# 05-GPS_IMU_SENSORS.net
KiCad netlist of a schematic drawn in Altium Designer
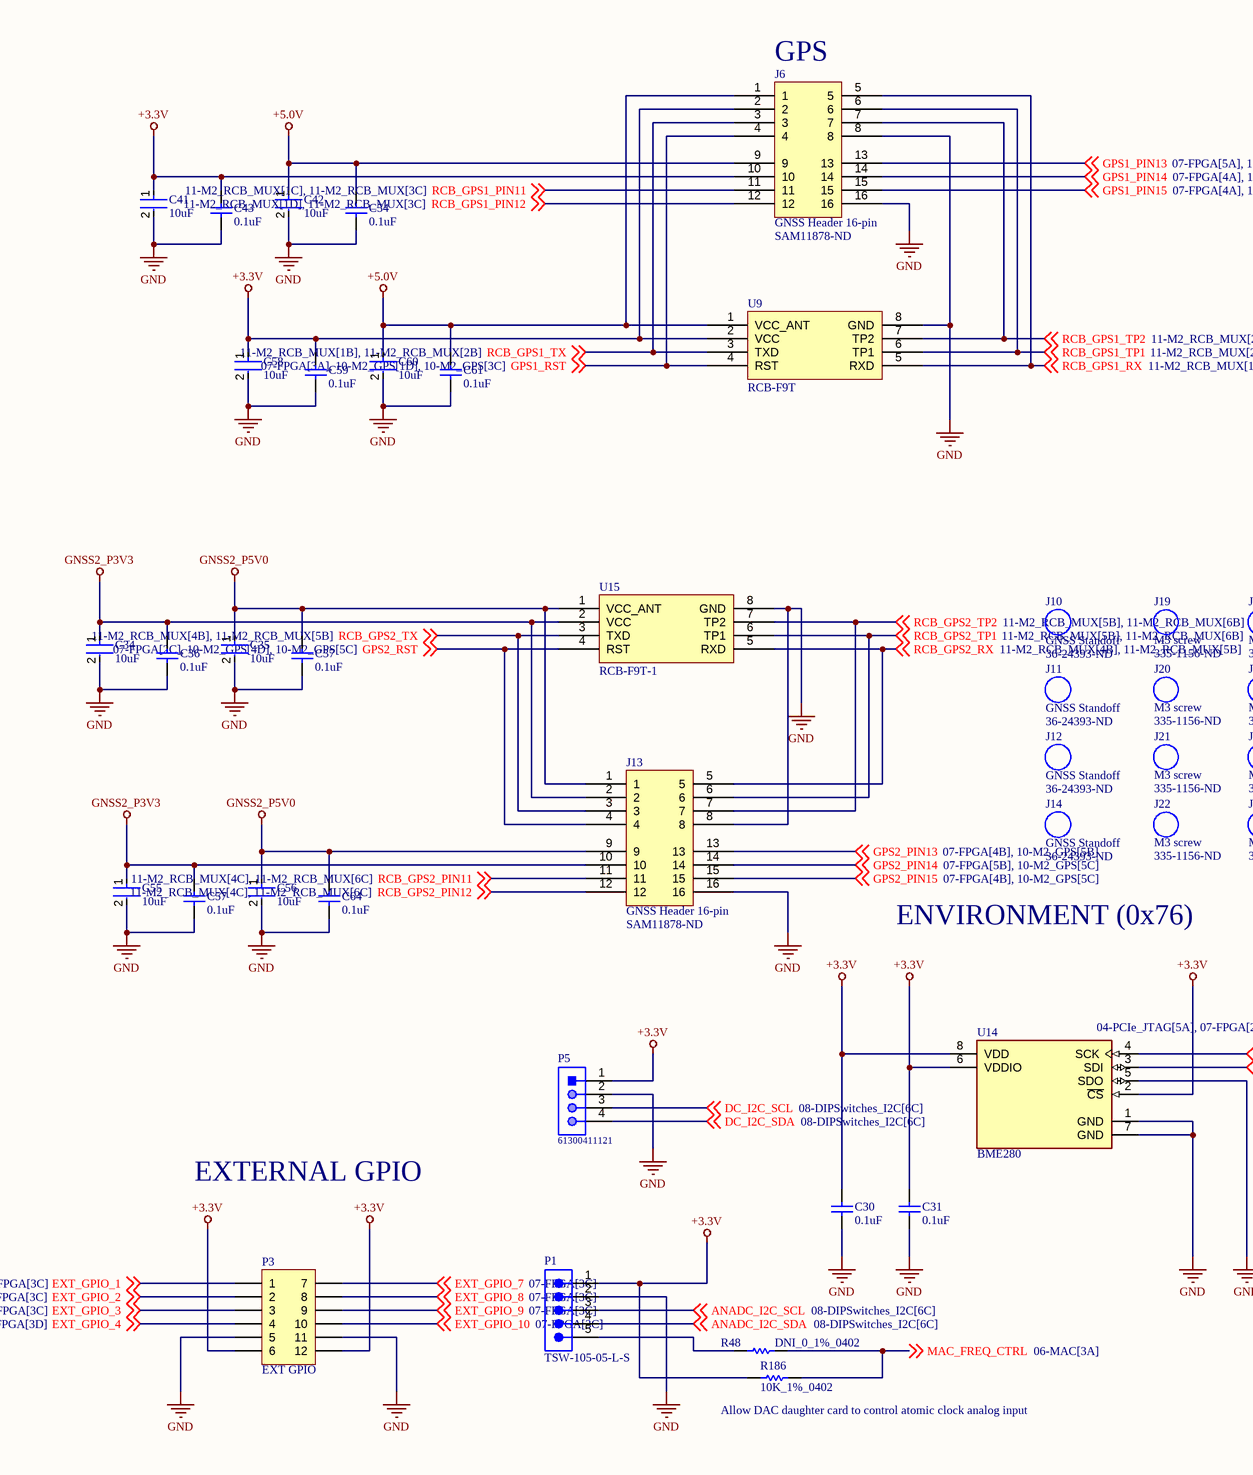
[diagram p0: 05-GPS_IMU_SENSORS.SchDoc, left]
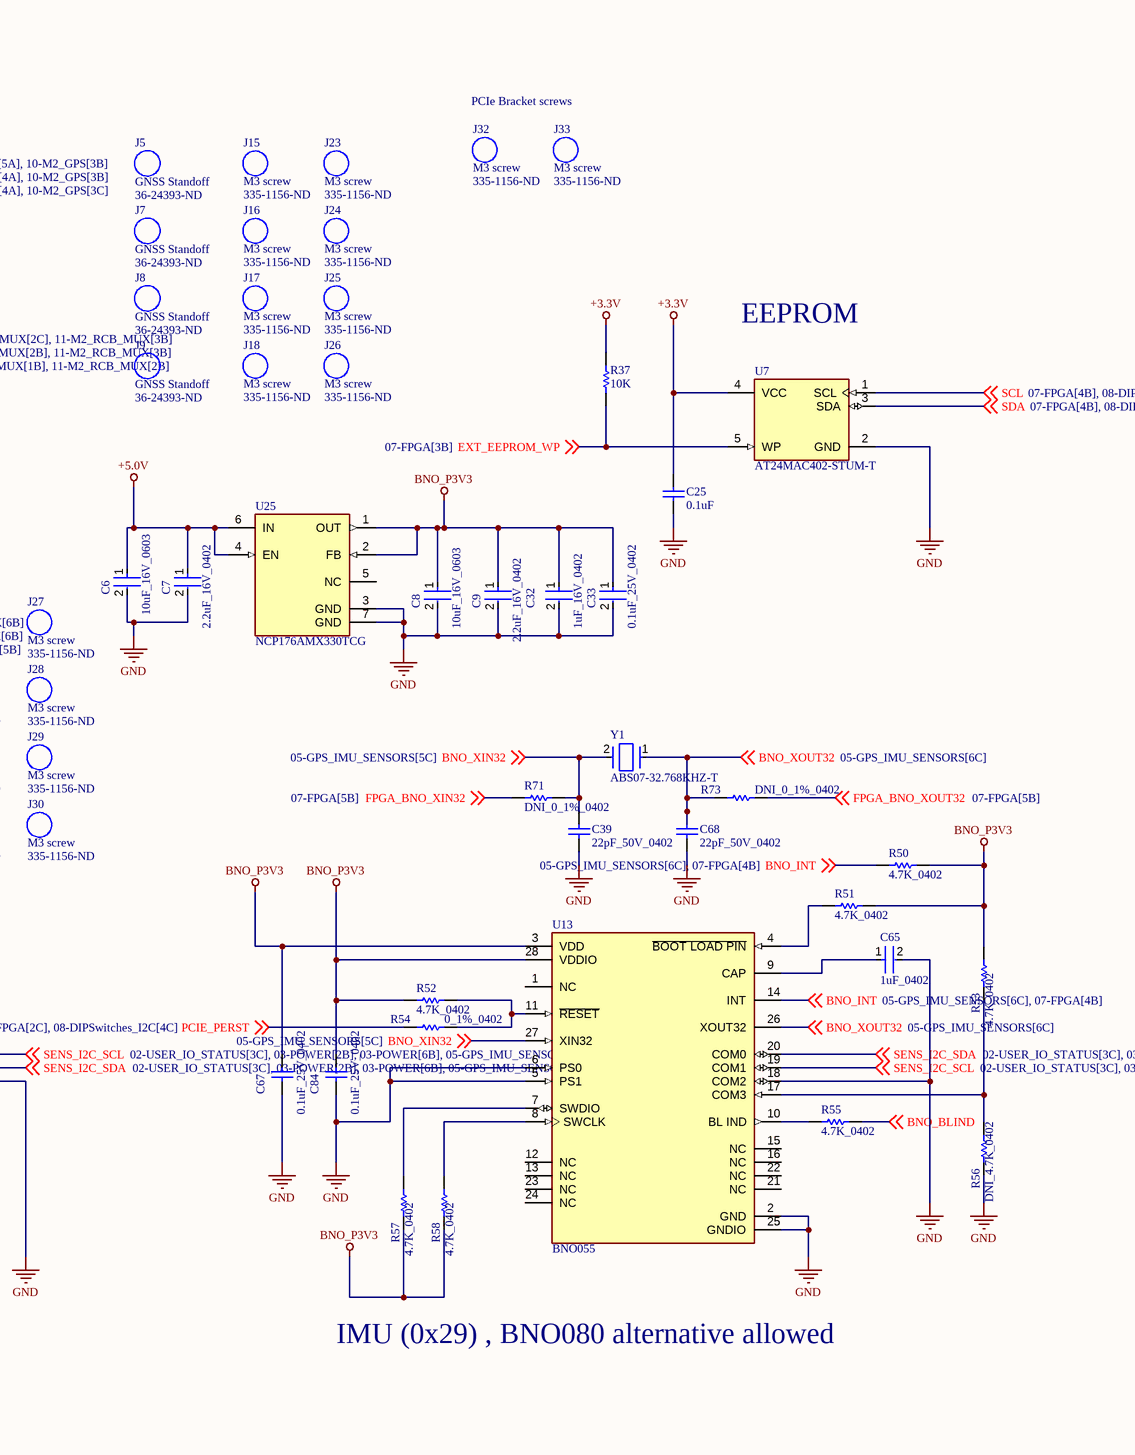
[diagram p1: 05-GPS_IMU_SENSORS.SchDoc, right]

(export (version "E")
  (design (tool "Eeschema 10.0.6"))
  (components
    (comp (ref "C6")
      (value "10uF_16V_0603")
      (footprint "FP-0603-L_1_6_0_2-W_0_8_0-MFG")
      (description "Multilayer Ceramic Capacitor 10uF 16V X5R 20% SMD 0603 T/R")
      (fields (field (name "TOLERANCE") "20%"))
      (libsource (lib "Altium Content Vault") (part "b4654b650e69147ec39a6b967a45e02"))
    )
    (comp (ref "C7")
      (value "2.2uF_16V_0402")
      (footprint "FP-C1005-050-0_05-IPC_A")
      (description "Multilayer Ceramic Capacitors 2.2μF ±10% 16V X5R SMD 0402")
      (fields (field (name "TOLERANCE") "10%"))
      (libsource (lib "Altium Content Vault") (part "b4654b650e69147ec39a6b967a45e02"))
    )
    (comp (ref "C8")
      (value "10uF_16V_0603")
      (footprint "FP-0603-L_1_6_0_2-W_0_8_0-MFG")
      (description "Multilayer Ceramic Capacitor 10uF 16V X5R 20% SMD 0603 T/R")
      (fields (field (name "TOLERANCE") "20%"))
      (libsource (lib "Altium Content Vault") (part "b4654b650e69147ec39a6b967a45e02"))
    )
    (comp (ref "C9")
      (value "2.2uF_16V_0402")
      (footprint "FP-C1005-050-0_05-IPC_A")
      (description "Multilayer Ceramic Capacitors 2.2μF ±10% 16V X5R SMD 0402")
      (fields (field (name "TOLERANCE") "10%"))
      (libsource (lib "Altium Content Vault") (part "b4654b650e69147ec39a6b967a45e02"))
    )
    (comp (ref "C25")
      (value "0.1uF")
      (footprint "CAPC1608X87X45ML20T05")
      (description "C0603X104K5RACAUTO")
      (fields (field (name "MANUFACTURER") "Kemet"))
      (libsource (lib "Altium Content Vault") (part "CAP"))
    )
    (comp (ref "C30")
      (value "0.1uF")
      (footprint "CAPC1608X87X45ML20T05")
      (description "C0603X104K5RACAUTO")
      (fields (field (name "MANUFACTURER") "Kemet"))
      (libsource (lib "Altium Content Vault") (part "CAP"))
    )
    (comp (ref "C31")
      (value "0.1uF")
      (footprint "CAPC1608X87X45ML20T05")
      (description "C0603X104K5RACAUTO")
      (fields (field (name "MANUFACTURER") "Kemet"))
      (libsource (lib "Altium Content Vault") (part "CAP"))
    )
    (comp (ref "C32")
      (value "1uF_16V_0402")
      (footprint "FP-0402-L_1_0_0_05-W_0_5-IPC_A")
      (description "None")
      (fields (field (name "TOLERANCE") "10%"))
      (libsource (lib "Altium Content Vault") (part "b4654b650e69147ec39a6b967a45e02"))
    )
    (comp (ref "C33")
      (value "0.1uF_25V_0402")
      (footprint "FP-0402-L_1_0_1-W_0_5_0_1-IPC_C")
      (description "General Purpose Ceramic Capacitor, 0402, 100nF, 10%, X7R, 15%, 25V")
      (fields (field (name "VOLTAGE") "25V") (field (name "TOLERANCE") "10%"))
      (libsource (lib "Altium Content Vault") (part "b4654b650e69147ec39a6b967a45e02"))
    )
    (comp (ref "C34")
      (value "10uF")
      (footprint "FP-MK212BG-MFG")
      (description "None")
      (fields (field (name "TOLERANCE") "10%") (field (name "VOLTAGE") "16V"))
      (libsource (lib "Altium Content Vault") (part "b4654b650e69147ec39a6b967a45e02"))
    )
    (comp (ref "C35")
      (value "10uF")
      (footprint "FP-MK212BG-MFG")
      (description "None")
      (fields (field (name "TOLERANCE") "10%") (field (name "VOLTAGE") "16V"))
      (libsource (lib "Altium Content Vault") (part "b4654b650e69147ec39a6b967a45e02"))
    )
    (comp (ref "C36")
      (value "0.1uF")
      (footprint "CAPC1608X87X45ML20T05")
      (description "C0603X104K5RACAUTO")
      (fields (field (name "MANUFACTURER") "Kemet"))
      (libsource (lib "Altium Content Vault") (part "CAP"))
    )
    (comp (ref "C37")
      (value "0.1uF")
      (footprint "CAPC1608X87X45ML20T05")
      (description "C0603X104K5RACAUTO")
      (fields (field (name "MANUFACTURER") "Kemet"))
      (libsource (lib "Altium Content Vault") (part "CAP"))
    )
    (comp (ref "C39")
      (value "22pF_50V_0402")
      (footprint "CAPC1005X55X25ML05T05")
      (description "Chip Capacitor, 22 pF, +/- 5%, 50 V, -55 to 125 degC, 0402 (1005 Metric), RoHS, Tape and Reel")
      (fields (field (name "MANUFACTURER") "Yageo") (field (name "TOLERANCE") "5%"))
      (libsource (lib "Altium Content Vault") (part "CAP-NP-2"))
    )
    (comp (ref "C41")
      (value "10uF")
      (footprint "FP-MK212BG-MFG")
      (description "None")
      (fields (field (name "TOLERANCE") "10%") (field (name "VOLTAGE") "16V"))
      (libsource (lib "Altium Content Vault") (part "b4654b650e69147ec39a6b967a45e02"))
    )
    (comp (ref "C42")
      (value "10uF")
      (footprint "FP-MK212BG-MFG")
      (description "None")
      (fields (field (name "TOLERANCE") "10%") (field (name "VOLTAGE") "16V"))
      (libsource (lib "Altium Content Vault") (part "b4654b650e69147ec39a6b967a45e02"))
    )
    (comp (ref "C43")
      (value "0.1uF")
      (footprint "CAPC1608X87X45ML20T05")
      (description "C0603X104K5RACAUTO")
      (fields (field (name "MANUFACTURER") "Kemet"))
      (libsource (lib "Altium Content Vault") (part "CAP"))
    )
    (comp (ref "C54")
      (value "0.1uF")
      (footprint "CAPC1608X87X45ML20T05")
      (description "C0603X104K5RACAUTO")
      (fields (field (name "MANUFACTURER") "Kemet"))
      (libsource (lib "Altium Content Vault") (part "CAP"))
    )
    (comp (ref "C55")
      (value "10uF")
      (footprint "FP-MK212BG-MFG")
      (description "None")
      (fields (field (name "TOLERANCE") "10%") (field (name "VOLTAGE") "16V"))
      (libsource (lib "Altium Content Vault") (part "b4654b650e69147ec39a6b967a45e02"))
    )
    (comp (ref "C56")
      (value "10uF")
      (footprint "FP-MK212BG-MFG")
      (description "None")
      (fields (field (name "TOLERANCE") "10%") (field (name "VOLTAGE") "16V"))
      (libsource (lib "Altium Content Vault") (part "b4654b650e69147ec39a6b967a45e02"))
    )
    (comp (ref "C57")
      (value "0.1uF")
      (footprint "CAPC1608X87X45ML20T05")
      (description "C0603X104K5RACAUTO")
      (fields (field (name "MANUFACTURER") "Kemet"))
      (libsource (lib "Altium Content Vault") (part "CAP"))
    )
    (comp (ref "C58")
      (value "10uF")
      (footprint "FP-MK212BG-MFG")
      (description "None")
      (fields (field (name "TOLERANCE") "10%") (field (name "VOLTAGE") "16V"))
      (libsource (lib "Altium Content Vault") (part "b4654b650e69147ec39a6b967a45e02"))
    )
    (comp (ref "C59")
      (value "0.1uF")
      (footprint "CAPC1608X87X45ML20T05")
      (description "C0603X104K5RACAUTO")
      (fields (field (name "MANUFACTURER") "Kemet"))
      (libsource (lib "Altium Content Vault") (part "CAP"))
    )
    (comp (ref "C60")
      (value "10uF")
      (footprint "FP-MK212BG-MFG")
      (description "None")
      (fields (field (name "TOLERANCE") "10%") (field (name "VOLTAGE") "16V"))
      (libsource (lib "Altium Content Vault") (part "b4654b650e69147ec39a6b967a45e02"))
    )
    (comp (ref "C61")
      (value "0.1uF")
      (footprint "CAPC1608X87X45ML20T05")
      (description "C0603X104K5RACAUTO")
      (fields (field (name "MANUFACTURER") "Kemet"))
      (libsource (lib "Altium Content Vault") (part "CAP"))
    )
    (comp (ref "C64")
      (value "0.1uF")
      (footprint "CAPC1608X87X45ML20T05")
      (description "C0603X104K5RACAUTO")
      (fields (field (name "MANUFACTURER") "Kemet"))
      (libsource (lib "Altium Content Vault") (part "CAP"))
    )
    (comp (ref "C65")
      (value "1uF_0402")
      (footprint "FP-0402-L_1_0_0_05-W_0_5-IPC_C")
      (description "None")
      (fields (field (name "TOLERANCE") "20%") (field (name "VOLTAGE") "16V"))
      (libsource (lib "Altium Content Vault") (part "b4654b650e69147ec39a6b967a45e02"))
    )
    (comp (ref "C67")
      (value "0.1uF_25V_0402")
      (footprint "CAPC1005X56X25NL10T15")
      (fields
        (field (name "PART NUMBER") "04023D104KAT2A")
        (field (name "MANUFACTURER") "AVX Interconnect / Elco")
      )
      (libsource (lib "Altium Content Vault") (part "CAP"))
    )
    (comp (ref "C68")
      (value "22pF_50V_0402")
      (footprint "CAPC1005X55X25ML05T05")
      (description "Chip Capacitor, 22 pF, +/- 5%, 50 V, -55 to 125 degC, 0402 (1005 Metric), RoHS, Tape and Reel")
      (fields (field (name "MANUFACTURER") "Yageo") (field (name "TOLERANCE") "5%"))
      (libsource (lib "Altium Content Vault") (part "CAP-NP-2"))
    )
    (comp (ref "C84")
      (value "0.1uF_25V_0402")
      (footprint "CAPC1005X56X25NL10T15")
      (fields
        (field (name "PART NUMBER") "04023D104KAT2A")
        (field (name "MANUFACTURER") "AVX Interconnect / Elco")
      )
      (libsource (lib "Altium Content Vault") (part "CAP"))
    )
    (comp (ref "J5")
      (value "GNSS Standoff")
      (fields (field (name "SUPPLIER PART NUMBER 1") "36-24393-ND"))
      (libsource (lib "FPGA_CONN") (part "GNSS Standoff"))
    )
    (comp (ref "J6")
      (value "GNSS Header 16-pin")
      (footprint "GNSS Header 16-pin")
      (fields (field (name "SUPPLIER PART NUMBER 1") "SAM11878-ND"))
      (libsource (lib "FPGA_CONN") (part "GNSS Header 16-pin"))
    )
    (comp (ref "J7")
      (value "GNSS Standoff")
      (fields (field (name "SUPPLIER PART NUMBER 1") "36-24393-ND"))
      (libsource (lib "FPGA_CONN") (part "GNSS Standoff"))
    )
    (comp (ref "J8")
      (value "GNSS Standoff")
      (fields (field (name "SUPPLIER PART NUMBER 1") "36-24393-ND"))
      (libsource (lib "FPGA_CONN") (part "GNSS Standoff"))
    )
    (comp (ref "J9")
      (value "GNSS Standoff")
      (fields (field (name "SUPPLIER PART NUMBER 1") "36-24393-ND"))
      (libsource (lib "FPGA_CONN") (part "GNSS Standoff"))
    )
    (comp (ref "J10")
      (value "GNSS Standoff")
      (fields (field (name "SUPPLIER PART NUMBER 1") "36-24393-ND"))
      (libsource (lib "FPGA_CONN") (part "GNSS Standoff"))
    )
    (comp (ref "J11")
      (value "GNSS Standoff")
      (fields (field (name "SUPPLIER PART NUMBER 1") "36-24393-ND"))
      (libsource (lib "FPGA_CONN") (part "GNSS Standoff"))
    )
    (comp (ref "J12")
      (value "GNSS Standoff")
      (fields (field (name "SUPPLIER PART NUMBER 1") "36-24393-ND"))
      (libsource (lib "FPGA_CONN") (part "GNSS Standoff"))
    )
    (comp (ref "J13")
      (value "GNSS Header 16-pin")
      (footprint "GNSS Header 16-pin")
      (fields (field (name "SUPPLIER PART NUMBER 1") "SAM11878-ND"))
      (libsource (lib "FPGA_CONN") (part "GNSS Header 16-pin"))
    )
    (comp (ref "J14")
      (value "GNSS Standoff")
      (fields (field (name "SUPPLIER PART NUMBER 1") "36-24393-ND"))
      (libsource (lib "FPGA_CONN") (part "GNSS Standoff"))
    )
    (comp (ref "J15")
      (value "M3 screw")
      (fields (field (name "SUPPLIER PART NUMBER 1") "335-1156-ND"))
      (libsource (lib "FPGA_CONN") (part "M3 screw"))
    )
    (comp (ref "J16")
      (value "M3 screw")
      (fields (field (name "SUPPLIER PART NUMBER 1") "335-1156-ND"))
      (libsource (lib "FPGA_CONN") (part "M3 screw"))
    )
    (comp (ref "J17")
      (value "M3 screw")
      (fields (field (name "SUPPLIER PART NUMBER 1") "335-1156-ND"))
      (libsource (lib "FPGA_CONN") (part "M3 screw"))
    )
    (comp (ref "J18")
      (value "M3 screw")
      (fields (field (name "SUPPLIER PART NUMBER 1") "335-1156-ND"))
      (libsource (lib "FPGA_CONN") (part "M3 screw"))
    )
    (comp (ref "J19")
      (value "M3 screw")
      (fields (field (name "SUPPLIER PART NUMBER 1") "335-1156-ND"))
      (libsource (lib "FPGA_CONN") (part "M3 screw"))
    )
    (comp (ref "J20")
      (value "M3 screw")
      (fields (field (name "SUPPLIER PART NUMBER 1") "335-1156-ND"))
      (libsource (lib "FPGA_CONN") (part "M3 screw"))
    )
    (comp (ref "J21")
      (value "M3 screw")
      (fields (field (name "SUPPLIER PART NUMBER 1") "335-1156-ND"))
      (libsource (lib "FPGA_CONN") (part "M3 screw"))
    )
    (comp (ref "J22")
      (value "M3 screw")
      (fields (field (name "SUPPLIER PART NUMBER 1") "335-1156-ND"))
      (libsource (lib "FPGA_CONN") (part "M3 screw"))
    )
    (comp (ref "J23")
      (value "M3 screw")
      (fields (field (name "SUPPLIER PART NUMBER 1") "335-1156-ND"))
      (libsource (lib "FPGA_CONN") (part "M3 screw"))
    )
    (comp (ref "J24")
      (value "M3 screw")
      (fields (field (name "SUPPLIER PART NUMBER 1") "335-1156-ND"))
      (libsource (lib "FPGA_CONN") (part "M3 screw"))
    )
    (comp (ref "J25")
      (value "M3 screw")
      (fields (field (name "SUPPLIER PART NUMBER 1") "335-1156-ND"))
      (libsource (lib "FPGA_CONN") (part "M3 screw"))
    )
    (comp (ref "J26")
      (value "M3 screw")
      (fields (field (name "SUPPLIER PART NUMBER 1") "335-1156-ND"))
      (libsource (lib "FPGA_CONN") (part "M3 screw"))
    )
    (comp (ref "J27")
      (value "M3 screw")
      (fields (field (name "SUPPLIER PART NUMBER 1") "335-1156-ND"))
      (libsource (lib "FPGA_CONN") (part "M3 screw"))
    )
    (comp (ref "J28")
      (value "M3 screw")
      (fields (field (name "SUPPLIER PART NUMBER 1") "335-1156-ND"))
      (libsource (lib "FPGA_CONN") (part "M3 screw"))
    )
    (comp (ref "J29")
      (value "M3 screw")
      (fields (field (name "SUPPLIER PART NUMBER 1") "335-1156-ND"))
      (libsource (lib "FPGA_CONN") (part "M3 screw"))
    )
    (comp (ref "J30")
      (value "M3 screw")
      (fields (field (name "SUPPLIER PART NUMBER 1") "335-1156-ND"))
      (libsource (lib "FPGA_CONN") (part "M3 screw"))
    )
    (comp (ref "J32")
      (value "M3 screw")
      (fields (field (name "SUPPLIER PART NUMBER 1") "335-1156-ND"))
      (libsource (lib "FPGA_CONN") (part "M3 screw"))
    )
    (comp (ref "J33")
      (value "M3 screw")
      (fields (field (name "SUPPLIER PART NUMBER 1") "335-1156-ND"))
      (libsource (lib "FPGA_CONN") (part "M3 screw"))
    )
    (comp (ref "P1")
      (value "TSW-105-05-L-S")
      (footprint "SMTC-TSW-105-05-X-S")
      (description "0.025\" SQ Post Header, Through-hole, Vertical, -55 to 125 degC, 2.54 mm Pitch, 5-Pin, Male, RoHS")
      (fields (field (name "MANUFACTURER") "Samtec"))
      (libsource (lib "Altium Content Vault") (part "SMTC-TSW-105-05-X-S"))
    )
    (comp (ref "P3")
      (value "EXT GPIO")
      (footprint "HDR2X6_CEN")
      (description "Header, 6-Pin, Dual row")
      (fields (field (name "PUBLISHER") "Altium Limited"))
      (libsource (lib "Miscellaneous Connectors") (part "Header 6X2A"))
    )
    (comp (ref "P5")
      (value "61300411121")
      (footprint "61300411121")
      (description "THT Vertical Pin Header WR-PHD, Pitch 2.54 mm, Single Row, 4 pins")
      (fields (field (name "MANUFACTURER") "Wurth Elektronik") (field (name "PUBLISHER") "WurthElektronik"))
      (libsource (lib "Altium Content Vault") (part "WE-CN-1P-M-R4"))
    )
    (comp (ref "R37")
      (value "10K")
      (footprint "RESC1608X55X30LL15T20")
      (fields (field (name "TOLERANCE") "±1%") (field (name "MANUFACTURER") "Stackpole-Electronics-Inc."))
      (libsource (lib "Altium Content Vault") (part "RES-2"))
    )
    (comp (ref "R48")
      (value "DNI_0_1%_0402")
      (footprint "RESC1005X40X25LL05T05")
      (description "Chip Resistor, 0 Ohm, 0.1 W, -55 to 155 degC, 0402 (1005 Metric), RoHS, Tape and Reel")
      (fields (field (name "MANUFACTURER") "Panasonic") (field (name "TOLERANCE") "5%"))
      (libsource (lib "Altium Content Vault") (part "RES-2"))
    )
    (comp (ref "R50")
      (value "4.7K_0402")
      (footprint "RESC1005X40X25LL05T05")
      (description "Chip Resistor, 4.7 KOhm, +/- 1%, 0.1 W, -55 to 155 degC, 0402 (1005 Metric), RoHS, Tape and Reel")
      (fields (field (name "TOLERANCE") "1%") (field (name "PARTNUMBER") "ERJ-2RKF4701X"))
      (libsource (lib "Altium Content Vault") (part "RES-2"))
    )
    (comp (ref "R51")
      (value "4.7K_0402")
      (footprint "RESC1005X40X25LL05T05")
      (description "Chip Resistor, 4.7 KOhm, +/- 1%, 0.1 W, -55 to 155 degC, 0402 (1005 Metric), RoHS, Tape and Reel")
      (fields (field (name "TOLERANCE") "1%") (field (name "PARTNUMBER") "ERJ-2RKF4701X"))
      (libsource (lib "Altium Content Vault") (part "RES-2"))
    )
    (comp (ref "R52")
      (value "4.7K_0402")
      (footprint "RESC1005X40X25LL05T05")
      (description "Chip Resistor, 4.7 KOhm, +/- 1%, 0.1 W, -55 to 155 degC, 0402 (1005 Metric), RoHS, Tape and Reel")
      (fields (field (name "TOLERANCE") "1%") (field (name "PARTNUMBER") "ERJ-2RKF4701X"))
      (libsource (lib "Altium Content Vault") (part "RES-2"))
    )
    (comp (ref "R53")
      (value "4.7K_0402")
      (footprint "RESC1005X40X25LL05T05")
      (description "Chip Resistor, 4.7 KOhm, +/- 1%, 0.1 W, -55 to 155 degC, 0402 (1005 Metric), RoHS, Tape and Reel")
      (fields (field (name "TOLERANCE") "1%") (field (name "PARTNUMBER") "ERJ-2RKF4701X"))
      (libsource (lib "Altium Content Vault") (part "RES-2"))
    )
    (comp (ref "R54")
      (value "0_1%_0402")
      (footprint "RESC1005X40X25LL05T05")
      (description "Chip Resistor, 0 Ohm, 0.1 W, -55 to 155 degC, 0402 (1005 Metric), RoHS, Tape and Reel")
      (fields (field (name "MANUFACTURER") "Panasonic") (field (name "TOLERANCE") "5%"))
      (libsource (lib "Altium Content Vault") (part "RES-2"))
    )
    (comp (ref "R55")
      (value "4.7K_0402")
      (footprint "RESC1005X40X25LL05T05")
      (description "Chip Resistor, 4.7 KOhm, +/- 1%, 0.1 W, -55 to 155 degC, 0402 (1005 Metric), RoHS, Tape and Reel")
      (fields (field (name "TOLERANCE") "1%") (field (name "PARTNUMBER") "ERJ-2RKF4701X"))
      (libsource (lib "Altium Content Vault") (part "RES-2"))
    )
    (comp (ref "R56")
      (value "DNI_4.7K_0402")
      (footprint "RESC1005X40X25LL05T05")
      (description "Chip Resistor, 4.7 KOhm, +/- 1%, 0.1 W, -55 to 155 degC, 0402 (1005 Metric), RoHS, Tape and Reel")
      (fields (field (name "TOLERANCE") "1%") (field (name "PARTNUMBER") "ERJ-2RKF4701X"))
      (libsource (lib "Altium Content Vault") (part "RES-2"))
    )
    (comp (ref "R57")
      (value "4.7K_0402")
      (footprint "RESC1005X40X25LL05T05")
      (description "Chip Resistor, 4.7 KOhm, +/- 1%, 0.1 W, -55 to 155 degC, 0402 (1005 Metric), RoHS, Tape and Reel")
      (fields (field (name "TOLERANCE") "1%") (field (name "PARTNUMBER") "ERJ-2RKF4701X"))
      (libsource (lib "Altium Content Vault") (part "RES-2"))
    )
    (comp (ref "R58")
      (value "4.7K_0402")
      (footprint "RESC1005X40X25LL05T05")
      (description "Chip Resistor, 4.7 KOhm, +/- 1%, 0.1 W, -55 to 155 degC, 0402 (1005 Metric), RoHS, Tape and Reel")
      (fields (field (name "TOLERANCE") "1%") (field (name "PARTNUMBER") "ERJ-2RKF4701X"))
      (libsource (lib "Altium Content Vault") (part "RES-2"))
    )
    (comp (ref "R71")
      (value "DNI_0_1%_0402")
      (footprint "RESC1005X40X25LL05T05")
      (description "Chip Resistor, 0 Ohm, 0.1 W, -55 to 155 degC, 0402 (1005 Metric), RoHS, Tape and Reel")
      (fields (field (name "MANUFACTURER") "Panasonic") (field (name "TOLERANCE") "5%"))
      (libsource (lib "Altium Content Vault") (part "RES-2"))
    )
    (comp (ref "R73")
      (value "DNI_0_1%_0402")
      (footprint "RESC1005X40X25LL05T05")
      (description "Chip Resistor, 0 Ohm, 0.1 W, -55 to 155 degC, 0402 (1005 Metric), RoHS, Tape and Reel")
      (fields (field (name "MANUFACTURER") "Panasonic") (field (name "TOLERANCE") "5%"))
      (libsource (lib "Altium Content Vault") (part "RES-2"))
    )
    (comp (ref "R186")
      (value "10K_1%_0402")
      (footprint "RESC1005X40X25LL05T10")
      (fields (field (name "PART NUMBER") "RC0402FR-0710KL") (field (name "MANUFACTURER") "Yageo / Phycomp"))
      (libsource (lib "Altium Content Vault") (part "RES"))
    )
    (comp (ref "U7")
      (value "AT24MAC402-STUM-T")
      (footprint "FP-5TS1-IPC_C")
      (description "IC EEPROM 2K I2C 1MHZ SOT23-5")
      (fields
        (field (name "MANUFACTURER") "Microchip")
        (field (name "OCTOPART") "https://octopart.com/at24mac402-stum-t-microchip-77758112")
      )
      (libsource (lib "Altium Content Vault") (part "93fe34f5f049140596bab6421a6454b"))
    )
    (comp (ref "U9")
      (value "RCB-F9T")
      (footprint "GNSS")
      (description "MOD, GPS")
      (fields (field (name "VELENTIUM PART NUM") "<V PART NUM>"))
      (libsource (lib "Modules") (part "RCB-F9T"))
    )
    (comp (ref "U13")
      (value "BNO055")
      (footprint "FP-BNO055-MFG")
      (description "IMU ACCEL/GYRO/MAG I2C 28LGA")
      (libsource (lib "Altium Content Vault") (part "ba837af00a0b6167256f888b31462b1"))
    )
    (comp (ref "U14")
      (value "BME280")
      (footprint "FP-BME280-MFG")
      (description "SENSOR PRESSURE HUMIDITY TEMP")
      (libsource (lib "Altium Content Vault") (part "d58e2f6669bc67e6a2bc6a28610ca79"))
    )
    (comp (ref "U15")
      (value "RCB-F9T-1")
      (footprint "GNSS")
      (description "MOD, GPS")
      (fields (field (name "VELENTIUM PART NUM") "<V PART NUM>"))
      (libsource (lib "Modules") (part "RCB-F9T"))
    )
    (comp (ref "U25")
      (value "NCP176AMX330TCG")
      (footprint "FP-711AT-MFG")
      (description "IC REG LINEAR 3.3V 500MA 6XDFN")
      (fields
        (field (name "MANUFACTURER") "ON Semiconductor")
        (field (name "OCTOPART") "https://octopart.com/ncp176amx330tcg-on+semiconductor-61522616")
      )
      (libsource (lib "Altium Content Vault") (part "a38d0f79c2a9f01c07a7e52882ed186"))
    )
    (comp (ref "Y1")
      (value "ABS07-32.768KHZ-T")
      (footprint "FP-ABS07-MFG")
      (description "Crystal 32.768kHz ±20ppm (Tol) 12.5pF FUND 70kΩ 2-Pin CSMD T/R")
      (fields (field (name "TOLERANCE") "20ppm"))
      (libsource (lib "Altium Content Vault") (part "c23a69dc6c9e2f18f2079038eb95dd1"))
    )
  )
  (nets
    (net (code "1") (name "+3.3V") (class "Default")
      (node (ref "C25") (pin "2") (pinfunction "2_2") (pintype "passive"))
      (node (ref "C30") (pin "2") (pinfunction "2_2") (pintype "passive"))
      (node (ref "C31") (pin "2") (pinfunction "2_2") (pintype "passive"))
      (node (ref "C41") (pin "1") (pinfunction "1_1") (pintype "passive"))
      (node (ref "C43") (pin "2") (pinfunction "2_2") (pintype "passive"))
      (node (ref "C58") (pin "1") (pinfunction "1_1") (pintype "passive"))
      (node (ref "C59") (pin "2") (pinfunction "2_2") (pintype "passive"))
      (node (ref "J6") (pin "10") (pinfunction "10_10") (pintype "passive"))
      (node (ref "J6") (pin "2") (pinfunction "2_2") (pintype "passive"))
      (node (ref "P1") (pin "1") (pinfunction "1_1") (pintype "passive"))
      (node (ref "P3") (pin "12") (pinfunction "12_12") (pintype "passive"))
      (node (ref "P3") (pin "6") (pinfunction "6_6") (pintype "passive"))
      (node (ref "P5") (pin "1") (pinfunction "1_1") (pintype "passive"))
      (node (ref "R186") (pin "1") (pinfunction "1_1") (pintype "passive"))
      (node (ref "R37") (pin "2") (pinfunction "2_2") (pintype "passive"))
      (node (ref "U14") (pin "2") (pinfunction "~{CS}_2") (pintype "input"))
      (node (ref "U14") (pin "6") (pinfunction "VDDIO_6") (pintype "power_in"))
      (node (ref "U14") (pin "8") (pinfunction "VDD_8") (pintype "power_in"))
      (node (ref "U7") (pin "4") (pinfunction "VCC_4") (pintype "power_in"))
      (node (ref "U9") (pin "2") (pinfunction "VCC_2") (pintype "passive"))
    )
    (net (code "2") (name "+5.0V") (class "Default")
      (node (ref "C42") (pin "1") (pinfunction "1_1") (pintype "passive"))
      (node (ref "C54") (pin "2") (pinfunction "2_2") (pintype "passive"))
      (node (ref "C6") (pin "1") (pinfunction "1_1") (pintype "passive"))
      (node (ref "C60") (pin "1") (pinfunction "1_1") (pintype "passive"))
      (node (ref "C61") (pin "2") (pinfunction "2_2") (pintype "passive"))
      (node (ref "C7") (pin "1") (pinfunction "1_1") (pintype "passive"))
      (node (ref "J6") (pin "1") (pinfunction "1_1") (pintype "passive"))
      (node (ref "J6") (pin "9") (pinfunction "9_9") (pintype "passive"))
      (node (ref "U25") (pin "4") (pinfunction "EN_4") (pintype "input"))
      (node (ref "U25") (pin "6") (pinfunction "IN_6") (pintype "power_in"))
      (node (ref "U9") (pin "1") (pinfunction "VCC_ANT_1") (pintype "passive"))
    )
    (net (code "3") (name "ANADC_I2C_SCL") (class "Default")
      (node (ref "P1") (pin "3") (pinfunction "3_3") (pintype "passive"))
    )
    (net (code "4") (name "ANADC_I2C_SDA") (class "Default")
      (node (ref "P1") (pin "4") (pinfunction "4_4") (pintype "passive"))
    )
    (net (code "5") (name "BNO_BLIND") (class "Default")
      (node (ref "R55") (pin "1") (pinfunction "1_1") (pintype "passive"))
    )
    (net (code "6") (name "BNO_INT") (class "Default")
      (node (ref "R50") (pin "2") (pinfunction "2_2") (pintype "passive"))
      (node (ref "U13") (pin "14") (pinfunction "INT_14") (pintype "passive"))
    )
    (net (code "7") (name "BNO_P3V3") (class "Default")
      (node (ref "C32") (pin "1") (pinfunction "1_1") (pintype "passive"))
      (node (ref "C33") (pin "1") (pinfunction "1_1") (pintype "passive"))
      (node (ref "C67") (pin "2") (pinfunction "2_2") (pintype "passive"))
      (node (ref "C8") (pin "1") (pinfunction "1_1") (pintype "passive"))
      (node (ref "C84") (pin "2") (pinfunction "2_2") (pintype "passive"))
      (node (ref "C9") (pin "1") (pinfunction "1_1") (pintype "passive"))
      (node (ref "R50") (pin "1") (pinfunction "1_1") (pintype "passive"))
      (node (ref "R51") (pin "1") (pinfunction "1_1") (pintype "passive"))
      (node (ref "R52") (pin "2") (pinfunction "2_2") (pintype "passive"))
      (node (ref "R53") (pin "2") (pinfunction "2_2") (pintype "passive"))
      (node (ref "R57") (pin "1") (pinfunction "1_1") (pintype "passive"))
      (node (ref "R58") (pin "1") (pinfunction "1_1") (pintype "passive"))
      (node (ref "U13") (pin "28") (pinfunction "VDDIO_28") (pintype "power_in"))
      (node (ref "U13") (pin "3") (pinfunction "VDD_3") (pintype "power_in"))
      (node (ref "U25") (pin "1") (pinfunction "OUT_1") (pintype "output"))
      (node (ref "U25") (pin "2") (pinfunction "FB_2") (pintype "input"))
    )
    (net (code "8") (name "BNO_XIN32") (class "Default")
      (node (ref "C39") (pin "2") (pinfunction "2_2") (pintype "passive"))
      (node (ref "R71") (pin "1") (pinfunction "1_1") (pintype "passive"))
      (node (ref "U13") (pin "27") (pinfunction "XIN32_27") (pintype "input"))
      (node (ref "Y1") (pin "2") (pinfunction "2_2") (pintype "passive"))
    )
    (net (code "9") (name "BNO_XOUT32") (class "Default")
      (node (ref "C68") (pin "2") (pinfunction "2_2") (pintype "passive"))
      (node (ref "R73") (pin "1") (pinfunction "1_1") (pintype "passive"))
      (node (ref "U13") (pin "26") (pinfunction "XOUT32_26") (pintype "passive"))
      (node (ref "Y1") (pin "1") (pinfunction "1_1") (pintype "passive"))
    )
    (net (code "10") (name "DC_I2C_SCL") (class "Default")
      (node (ref "P5") (pin "3") (pinfunction "3_3") (pintype "passive"))
    )
    (net (code "11") (name "DC_I2C_SDA") (class "Default")
      (node (ref "P5") (pin "4") (pinfunction "4_4") (pintype "passive"))
    )
    (net (code "12") (name "EXT_EEPROM_WP") (class "Default")
      (node (ref "R37") (pin "1") (pinfunction "1_1") (pintype "passive"))
      (node (ref "U7") (pin "5") (pinfunction "WP_5") (pintype "input"))
    )
    (net (code "13") (name "EXT_GPIO_1") (class "Default")
      (node (ref "P3") (pin "1") (pinfunction "1_1") (pintype "passive"))
    )
    (net (code "14") (name "EXT_GPIO_2") (class "Default")
      (node (ref "P3") (pin "2") (pinfunction "2_2") (pintype "passive"))
    )
    (net (code "15") (name "EXT_GPIO_3") (class "Default")
      (node (ref "P3") (pin "3") (pinfunction "3_3") (pintype "passive"))
    )
    (net (code "16") (name "EXT_GPIO_4") (class "Default")
      (node (ref "P3") (pin "4") (pinfunction "4_4") (pintype "passive"))
    )
    (net (code "17") (name "EXT_GPIO_7") (class "Default")
      (node (ref "P3") (pin "7") (pinfunction "7_7") (pintype "passive"))
    )
    (net (code "18") (name "EXT_GPIO_8") (class "Default")
      (node (ref "P3") (pin "8") (pinfunction "8_8") (pintype "passive"))
    )
    (net (code "19") (name "EXT_GPIO_9") (class "Default")
      (node (ref "P3") (pin "9") (pinfunction "9_9") (pintype "passive"))
    )
    (net (code "20") (name "EXT_GPIO_10") (class "Default")
      (node (ref "P3") (pin "10") (pinfunction "10_10") (pintype "passive"))
    )
    (net (code "21") (name "FPGA_BNO_XIN32") (class "Default")
      (node (ref "R71") (pin "2") (pinfunction "2_2") (pintype "passive"))
    )
    (net (code "22") (name "FPGA_BNO_XOUT32") (class "Default")
      (node (ref "R73") (pin "2") (pinfunction "2_2") (pintype "passive"))
    )
    (net (code "23") (name "GND") (class "Default")
      (node (ref "C25") (pin "1") (pinfunction "1_1") (pintype "passive"))
      (node (ref "C30") (pin "1") (pinfunction "1_1") (pintype "passive"))
      (node (ref "C31") (pin "1") (pinfunction "1_1") (pintype "passive"))
      (node (ref "C32") (pin "2") (pinfunction "2_2") (pintype "passive"))
      (node (ref "C33") (pin "2") (pinfunction "2_2") (pintype "passive"))
      (node (ref "C34") (pin "2") (pinfunction "2_2") (pintype "passive"))
      (node (ref "C35") (pin "2") (pinfunction "2_2") (pintype "passive"))
      (node (ref "C36") (pin "1") (pinfunction "1_1") (pintype "passive"))
      (node (ref "C37") (pin "1") (pinfunction "1_1") (pintype "passive"))
      (node (ref "C39") (pin "1") (pinfunction "1_1") (pintype "passive"))
      (node (ref "C41") (pin "2") (pinfunction "2_2") (pintype "passive"))
      (node (ref "C42") (pin "2") (pinfunction "2_2") (pintype "passive"))
      (node (ref "C43") (pin "1") (pinfunction "1_1") (pintype "passive"))
      (node (ref "C54") (pin "1") (pinfunction "1_1") (pintype "passive"))
      (node (ref "C55") (pin "2") (pinfunction "2_2") (pintype "passive"))
      (node (ref "C56") (pin "2") (pinfunction "2_2") (pintype "passive"))
      (node (ref "C57") (pin "1") (pinfunction "1_1") (pintype "passive"))
      (node (ref "C58") (pin "2") (pinfunction "2_2") (pintype "passive"))
      (node (ref "C59") (pin "1") (pinfunction "1_1") (pintype "passive"))
      (node (ref "C6") (pin "2") (pinfunction "2_2") (pintype "passive"))
      (node (ref "C60") (pin "2") (pinfunction "2_2") (pintype "passive"))
      (node (ref "C61") (pin "1") (pinfunction "1_1") (pintype "passive"))
      (node (ref "C64") (pin "1") (pinfunction "1_1") (pintype "passive"))
      (node (ref "C65") (pin "2") (pinfunction "2_2") (pintype "passive"))
      (node (ref "C67") (pin "1") (pinfunction "1_1") (pintype "passive"))
      (node (ref "C68") (pin "1") (pinfunction "1_1") (pintype "passive"))
      (node (ref "C7") (pin "2") (pinfunction "2_2") (pintype "passive"))
      (node (ref "C8") (pin "2") (pinfunction "2_2") (pintype "passive"))
      (node (ref "C84") (pin "1") (pinfunction "1_1") (pintype "passive"))
      (node (ref "C9") (pin "2") (pinfunction "2_2") (pintype "passive"))
      (node (ref "J13") (pin "16") (pinfunction "16_16") (pintype "passive"))
      (node (ref "J13") (pin "8") (pinfunction "8_8") (pintype "passive"))
      (node (ref "J6") (pin "16") (pinfunction "16_16") (pintype "passive"))
      (node (ref "J6") (pin "8") (pinfunction "8_8") (pintype "passive"))
      (node (ref "P1") (pin "2") (pinfunction "2_2") (pintype "passive"))
      (node (ref "P3") (pin "11") (pinfunction "11_11") (pintype "passive"))
      (node (ref "P3") (pin "5") (pinfunction "5_5") (pintype "passive"))
      (node (ref "P5") (pin "2") (pinfunction "2_2") (pintype "passive"))
      (node (ref "R56") (pin "1") (pinfunction "1_1") (pintype "passive"))
      (node (ref "U13") (pin "18") (pinfunction "COM2_18") (pintype "bidirectional"))
      (node (ref "U13") (pin "2") (pinfunction "GND_2") (pintype "power_in"))
      (node (ref "U13") (pin "25") (pinfunction "GNDIO_25") (pintype "power_in"))
      (node (ref "U13") (pin "5") (pinfunction "PS1_5") (pintype "input"))
      (node (ref "U13") (pin "6") (pinfunction "PS0_6") (pintype "input"))
      (node (ref "U14") (pin "1") (pinfunction "GND_1") (pintype "power_in"))
      (node (ref "U14") (pin "5") (pinfunction "SDO_5") (pintype "bidirectional"))
      (node (ref "U14") (pin "7") (pinfunction "GND_7") (pintype "power_in"))
      (node (ref "U15") (pin "8") (pinfunction "GND_8") (pintype "passive"))
      (node (ref "U25") (pin "3") (pinfunction "GND_3") (pintype "power_in"))
      (node (ref "U25") (pin "7") (pinfunction "GND_7") (pintype "power_in"))
      (node (ref "U7") (pin "2") (pinfunction "GND_2") (pintype "power_in"))
      (node (ref "U9") (pin "8") (pinfunction "GND_8") (pintype "passive"))
    )
    (net (code "24") (name "GNSS2_P3V3") (class "Default")
      (node (ref "C34") (pin "1") (pinfunction "1_1") (pintype "passive"))
      (node (ref "C36") (pin "2") (pinfunction "2_2") (pintype "passive"))
      (node (ref "C55") (pin "1") (pinfunction "1_1") (pintype "passive"))
      (node (ref "C57") (pin "2") (pinfunction "2_2") (pintype "passive"))
      (node (ref "J13") (pin "10") (pinfunction "10_10") (pintype "passive"))
      (node (ref "J13") (pin "2") (pinfunction "2_2") (pintype "passive"))
      (node (ref "U15") (pin "2") (pinfunction "VCC_2") (pintype "passive"))
    )
    (net (code "25") (name "GNSS2_P5V0") (class "Default")
      (node (ref "C35") (pin "1") (pinfunction "1_1") (pintype "passive"))
      (node (ref "C37") (pin "2") (pinfunction "2_2") (pintype "passive"))
      (node (ref "C56") (pin "1") (pinfunction "1_1") (pintype "passive"))
      (node (ref "C64") (pin "2") (pinfunction "2_2") (pintype "passive"))
      (node (ref "J13") (pin "1") (pinfunction "1_1") (pintype "passive"))
      (node (ref "J13") (pin "9") (pinfunction "9_9") (pintype "passive"))
      (node (ref "U15") (pin "1") (pinfunction "VCC_ANT_1") (pintype "passive"))
    )
    (net (code "26") (name "GPS1_PIN13") (class "Default")
      (node (ref "J6") (pin "13") (pinfunction "13_13") (pintype "passive"))
    )
    (net (code "27") (name "GPS1_PIN14") (class "Default")
      (node (ref "J6") (pin "14") (pinfunction "14_14") (pintype "passive"))
    )
    (net (code "28") (name "GPS1_PIN15") (class "Default")
      (node (ref "J6") (pin "15") (pinfunction "15_15") (pintype "passive"))
    )
    (net (code "29") (name "GPS1_RST") (class "Default")
      (node (ref "J6") (pin "4") (pinfunction "4_4") (pintype "passive"))
      (node (ref "U9") (pin "4") (pinfunction "RST_4") (pintype "passive"))
    )
    (net (code "30") (name "GPS2_PIN13") (class "Default")
      (node (ref "J13") (pin "13") (pinfunction "13_13") (pintype "passive"))
    )
    (net (code "31") (name "GPS2_PIN14") (class "Default")
      (node (ref "J13") (pin "14") (pinfunction "14_14") (pintype "passive"))
    )
    (net (code "32") (name "GPS2_PIN15") (class "Default")
      (node (ref "J13") (pin "15") (pinfunction "15_15") (pintype "passive"))
    )
    (net (code "33") (name "GPS2_RST") (class "Default")
      (node (ref "J13") (pin "4") (pinfunction "4_4") (pintype "passive"))
      (node (ref "U15") (pin "4") (pinfunction "RST_4") (pintype "passive"))
    )
    (net (code "34") (name "MAC_FREQ_CTRL") (class "Default")
      (node (ref "R186") (pin "2") (pinfunction "2_2") (pintype "passive"))
      (node (ref "R48") (pin "2") (pinfunction "2_2") (pintype "passive"))
    )
    (net (code "35") (name "Net-(P1-Pad5)") (class "Default")
      (node (ref "P1") (pin "5") (pinfunction "5_5") (pintype "passive"))
      (node (ref "R48") (pin "1") (pinfunction "1_1") (pintype "passive"))
    )
    (net (code "36") (name "Net-(U13-BL_IND)") (class "Default")
      (node (ref "R55") (pin "2") (pinfunction "2_2") (pintype "passive"))
      (node (ref "U13") (pin "10") (pinfunction "BL_IND_10") (pintype "output"))
    )
    (net (code "37") (name "Net-(U13-CAP)") (class "Default")
      (node (ref "C65") (pin "1") (pinfunction "1_1") (pintype "passive"))
      (node (ref "U13") (pin "9") (pinfunction "CAP_9") (pintype "passive"))
    )
    (net (code "38") (name "Net-(U13-COM3)") (class "Default")
      (node (ref "R53") (pin "1") (pinfunction "1_1") (pintype "passive"))
      (node (ref "R56") (pin "2") (pinfunction "2_2") (pintype "passive"))
      (node (ref "U13") (pin "17") (pinfunction "COM3_17") (pintype "input"))
    )
    (net (code "39") (name "Net-(U13-SWCLK)") (class "Default")
      (node (ref "R58") (pin "2") (pinfunction "2_2") (pintype "passive"))
      (node (ref "U13") (pin "8") (pinfunction "SWCLK_8") (pintype "input"))
    )
    (net (code "40") (name "Net-(U13-SWDIO)") (class "Default")
      (node (ref "R57") (pin "2") (pinfunction "2_2") (pintype "passive"))
      (node (ref "U13") (pin "7") (pinfunction "SWDIO_7") (pintype "bidirectional"))
    )
    (net (code "41") (name "Net-(U13-~{BOOT_LOAD_PIN})") (class "Default")
      (node (ref "R51") (pin "2") (pinfunction "2_2") (pintype "passive"))
      (node (ref "U13") (pin "4") (pinfunction "~{BOOT_LOAD_PIN}_4") (pintype "input"))
    )
    (net (code "42") (name "Net-(U13-~{RESET})") (class "Default")
      (node (ref "R52") (pin "1") (pinfunction "1_1") (pintype "passive"))
      (node (ref "R54") (pin "2") (pinfunction "2_2") (pintype "passive"))
      (node (ref "U13") (pin "11") (pinfunction "~{RESET}_11") (pintype "input"))
    )
    (net (code "43") (name "PCIE_PERST") (class "Default")
      (node (ref "R54") (pin "1") (pinfunction "1_1") (pintype "passive"))
    )
    (net (code "44") (name "RCB_GPS1_PIN11") (class "Default")
      (node (ref "J6") (pin "11") (pinfunction "11_11") (pintype "passive"))
    )
    (net (code "45") (name "RCB_GPS1_PIN12") (class "Default")
      (node (ref "J6") (pin "12") (pinfunction "12_12") (pintype "passive"))
    )
    (net (code "46") (name "RCB_GPS1_RX") (class "Default")
      (node (ref "J6") (pin "5") (pinfunction "5_5") (pintype "passive"))
      (node (ref "U9") (pin "5") (pinfunction "RXD_5") (pintype "passive"))
    )
    (net (code "47") (name "RCB_GPS1_TP1") (class "Default")
      (node (ref "J6") (pin "6") (pinfunction "6_6") (pintype "passive"))
      (node (ref "U9") (pin "6") (pinfunction "TP1_6") (pintype "passive"))
    )
    (net (code "48") (name "RCB_GPS1_TP2") (class "Default")
      (node (ref "J6") (pin "7") (pinfunction "7_7") (pintype "passive"))
      (node (ref "U9") (pin "7") (pinfunction "TP2_7") (pintype "passive"))
    )
    (net (code "49") (name "RCB_GPS1_TX") (class "Default")
      (node (ref "J6") (pin "3") (pinfunction "3_3") (pintype "passive"))
      (node (ref "U9") (pin "3") (pinfunction "TXD_3") (pintype "passive"))
    )
    (net (code "50") (name "RCB_GPS2_PIN11") (class "Default")
      (node (ref "J13") (pin "11") (pinfunction "11_11") (pintype "passive"))
    )
    (net (code "51") (name "RCB_GPS2_PIN12") (class "Default")
      (node (ref "J13") (pin "12") (pinfunction "12_12") (pintype "passive"))
    )
    (net (code "52") (name "RCB_GPS2_RX") (class "Default")
      (node (ref "J13") (pin "5") (pinfunction "5_5") (pintype "passive"))
      (node (ref "U15") (pin "5") (pinfunction "RXD_5") (pintype "passive"))
    )
    (net (code "53") (name "RCB_GPS2_TP1") (class "Default")
      (node (ref "J13") (pin "6") (pinfunction "6_6") (pintype "passive"))
      (node (ref "U15") (pin "6") (pinfunction "TP1_6") (pintype "passive"))
    )
    (net (code "54") (name "RCB_GPS2_TP2") (class "Default")
      (node (ref "J13") (pin "7") (pinfunction "7_7") (pintype "passive"))
      (node (ref "U15") (pin "7") (pinfunction "TP2_7") (pintype "passive"))
    )
    (net (code "55") (name "RCB_GPS2_TX") (class "Default")
      (node (ref "J13") (pin "3") (pinfunction "3_3") (pintype "passive"))
      (node (ref "U15") (pin "3") (pinfunction "TXD_3") (pintype "passive"))
    )
    (net (code "56") (name "SCL") (class "Default")
      (node (ref "U7") (pin "1") (pinfunction "SCL_1") (pintype "input"))
    )
    (net (code "57") (name "SDA") (class "Default")
      (node (ref "U7") (pin "3") (pinfunction "SDA_3") (pintype "bidirectional"))
    )
    (net (code "58") (name "SENS_I2C_SCL") (class "Default")
      (node (ref "U13") (pin "19") (pinfunction "COM1_19") (pintype "bidirectional"))
      (node (ref "U14") (pin "4") (pinfunction "SCK_4") (pintype "input"))
    )
    (net (code "59") (name "SENS_I2C_SDA") (class "Default")
      (node (ref "U13") (pin "20") (pinfunction "COM0_20") (pintype "bidirectional"))
      (node (ref "U14") (pin "3") (pinfunction "SDI_3") (pintype "bidirectional"))
    )
    (net (code "60") (name "unconnected-(U13-NC-Pad1)") (class "Default")
      (node (ref "U13") (pin "1") (pinfunction "NC_1") (pintype "passive"))
    )
    (net (code "61") (name "unconnected-(U13-NC-Pad12)") (class "Default")
      (node (ref "U13") (pin "12") (pinfunction "NC_12") (pintype "passive"))
    )
    (net (code "62") (name "unconnected-(U13-NC-Pad13)") (class "Default")
      (node (ref "U13") (pin "13") (pinfunction "NC_13") (pintype "passive"))
    )
    (net (code "63") (name "unconnected-(U13-NC-Pad15)") (class "Default")
      (node (ref "U13") (pin "15") (pinfunction "NC_15") (pintype "passive"))
    )
    (net (code "64") (name "unconnected-(U13-NC-Pad16)") (class "Default")
      (node (ref "U13") (pin "16") (pinfunction "NC_16") (pintype "passive"))
    )
    (net (code "65") (name "unconnected-(U13-NC-Pad21)") (class "Default")
      (node (ref "U13") (pin "21") (pinfunction "NC_21") (pintype "passive"))
    )
    (net (code "66") (name "unconnected-(U13-NC-Pad22)") (class "Default")
      (node (ref "U13") (pin "22") (pinfunction "NC_22") (pintype "passive"))
    )
    (net (code "67") (name "unconnected-(U13-NC-Pad23)") (class "Default")
      (node (ref "U13") (pin "23") (pinfunction "NC_23") (pintype "passive"))
    )
    (net (code "68") (name "unconnected-(U13-NC-Pad24)") (class "Default")
      (node (ref "U13") (pin "24") (pinfunction "NC_24") (pintype "passive"))
    )
    (net (code "69") (name "unconnected-(U25-NC-Pad5)") (class "Default")
      (node (ref "U25") (pin "5") (pinfunction "NC_5") (pintype "passive"))
    )
  )
)
